# OK_p_edzesilova.net
KiCad netlist of a schematic drawn in EAGLE
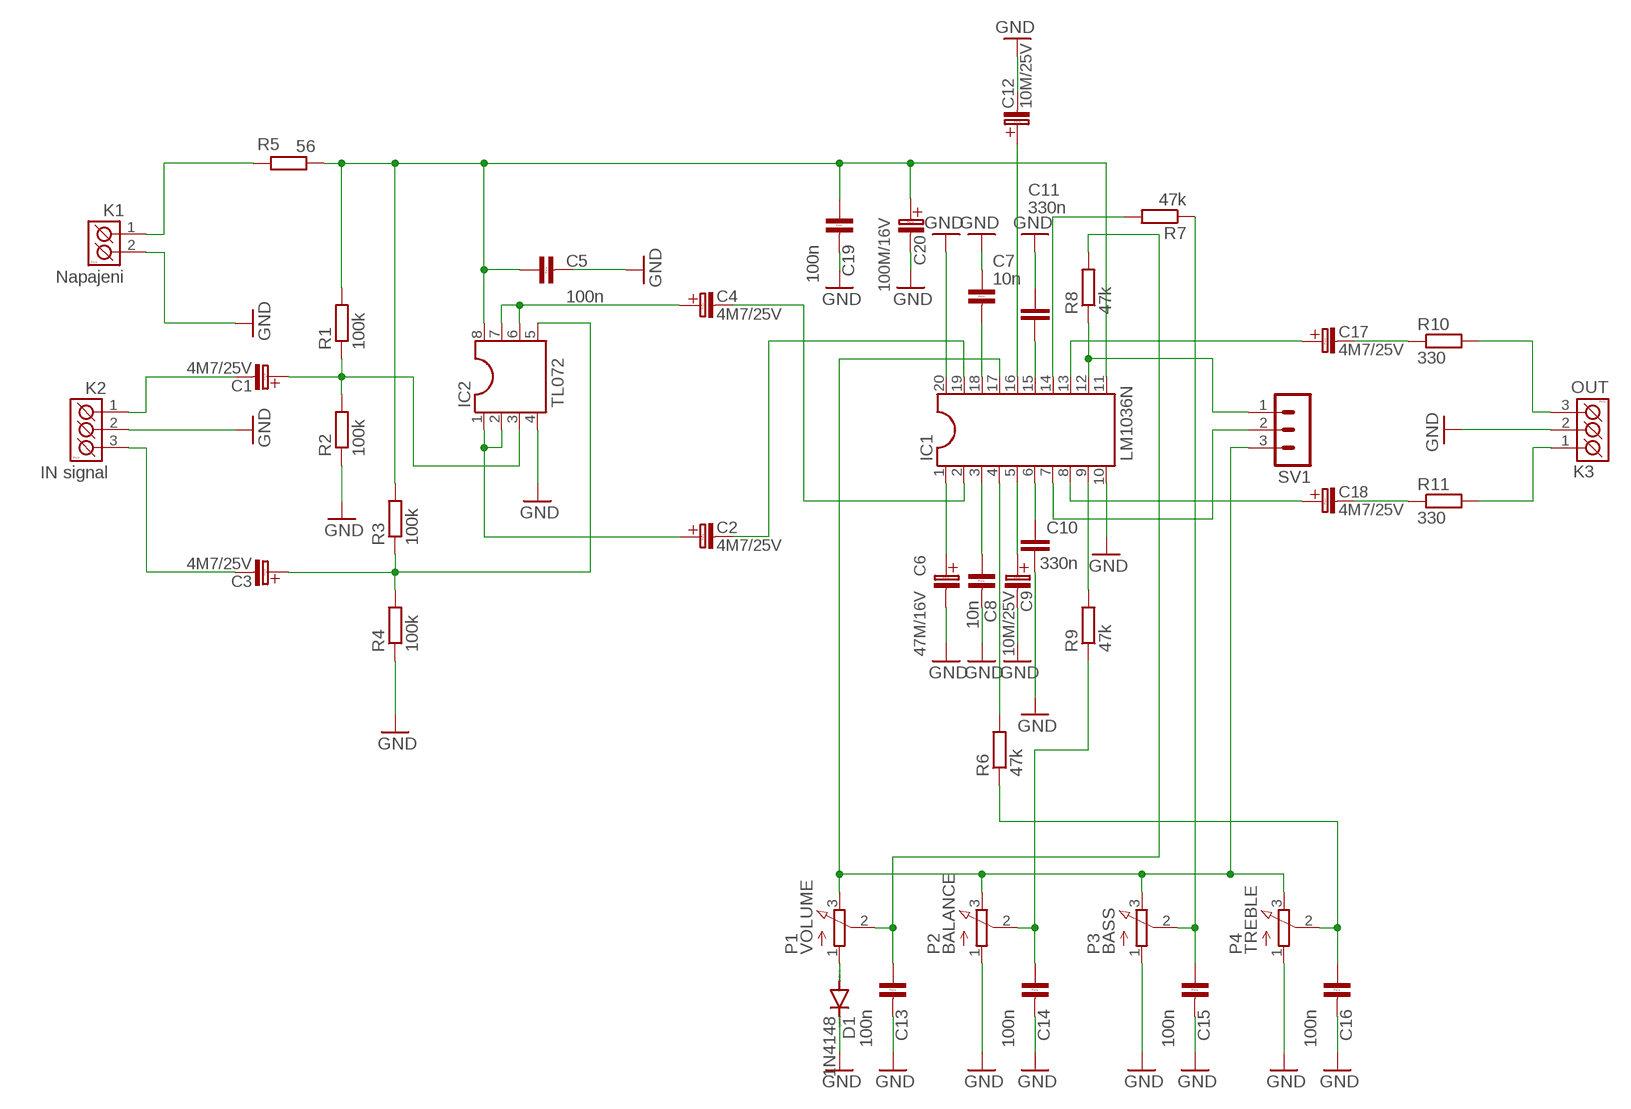
[diagram p0: schematic, sheet 1]

(export (version "E")
  (design (tool "Eeschema 10.0.6"))
  (components
    (comp (ref "C1")
      (value "4M7/25V")
      (footprint "eagle-import:C_EL_2")
      (libsource (lib "eagle-import") (part "4M7/63V"))
    )
    (comp (ref "C2")
      (value "4M7/25V")
      (footprint "eagle-import:C_EL_2")
      (libsource (lib "eagle-import") (part "4M7/63V"))
    )
    (comp (ref "C3")
      (value "4M7/25V")
      (footprint "eagle-import:C_EL_2")
      (libsource (lib "eagle-import") (part "4M7/63V"))
    )
    (comp (ref "C4")
      (value "4M7/25V")
      (footprint "eagle-import:C_EL_2")
      (libsource (lib "eagle-import") (part "4M7/63V"))
    )
    (comp (ref "C5")
      (value "100n")
      (footprint "eagle-import:RM5_2,5")
      (libsource (lib "eagle-import") (part "100N-J/63V"))
    )
    (comp (ref "C6")
      (value "47M/16V")
      (footprint "eagle-import:C_EL_2")
      (libsource (lib "eagle-import") (part "47M/10V"))
    )
    (comp (ref "C7")
      (value "10n")
      (footprint "eagle-import:RM5_2,5")
      (libsource (lib "eagle-import") (part "10N-J/63V"))
    )
    (comp (ref "C8")
      (value "10n")
      (footprint "eagle-import:RM5_2,5")
      (libsource (lib "eagle-import") (part "10N-J/63V"))
    )
    (comp (ref "C9")
      (value "10M/25V")
      (footprint "eagle-import:C_EL_2,5")
      (libsource (lib "eagle-import") (part "10M/100V"))
    )
    (comp (ref "C10")
      (value "330n")
      (footprint "eagle-import:C075-032X103")
      (libsource (lib "eagle-import") (part "C-EU075-032X103"))
    )
    (comp (ref "C11")
      (value "330n")
      (footprint "eagle-import:C075-032X103")
      (libsource (lib "eagle-import") (part "C-EU075-032X103"))
    )
    (comp (ref "C12")
      (value "10M/25V")
      (footprint "eagle-import:C_EL_2,5")
      (libsource (lib "eagle-import") (part "10M/100V"))
    )
    (comp (ref "C13")
      (value "100n")
      (footprint "eagle-import:RM5_2,5")
      (libsource (lib "eagle-import") (part "100N-J/63V"))
    )
    (comp (ref "C14")
      (value "100n")
      (footprint "eagle-import:RM5_2,5")
      (libsource (lib "eagle-import") (part "100N-J/63V"))
    )
    (comp (ref "C15")
      (value "100n")
      (footprint "eagle-import:RM5_2,5")
      (libsource (lib "eagle-import") (part "100N-J/63V"))
    )
    (comp (ref "C16")
      (value "100n")
      (footprint "eagle-import:RM5_2,5")
      (libsource (lib "eagle-import") (part "100N-J/63V"))
    )
    (comp (ref "C17")
      (value "4M7/25V")
      (footprint "eagle-import:C_EL_2")
      (libsource (lib "eagle-import") (part "4M7/63V"))
    )
    (comp (ref "C18")
      (value "4M7/25V")
      (footprint "eagle-import:C_EL_2")
      (libsource (lib "eagle-import") (part "4M7/63V"))
    )
    (comp (ref "C19")
      (value "100n")
      (footprint "eagle-import:RM5_2,5")
      (libsource (lib "eagle-import") (part "100N-J/63V"))
    )
    (comp (ref "C20")
      (value "100M/16V")
      (footprint "eagle-import:C_EL_3,5")
      (libsource (lib "eagle-import") (part "100M/50V"))
    )
    (comp (ref "D1")
      (value "1N4148")
      (footprint "eagle-import:DO35-7")
      (libsource (lib "eagle-import") (part "1N4148DO35-7"))
    )
    (comp (ref "IC1")
      (value "LM1036N")
      (footprint "eagle-import:DIL20")
      (libsource (lib "eagle-import") (part "DIL20"))
    )
    (comp (ref "IC2")
      (value "TL072")
      (footprint "eagle-import:DIL08")
      (libsource (lib "eagle-import") (part "DIL8"))
    )
    (comp (ref "K1")
      (value "Napajeni")
      (footprint "eagle-import:ARK500_2")
      (libsource (lib "eagle-import") (part "ARK500/2"))
    )
    (comp (ref "K2")
      (value "IN signal")
      (footprint "eagle-import:ARK500_3")
      (libsource (lib "eagle-import") (part "ARK500/3"))
    )
    (comp (ref "K3")
      (value "OUT")
      (footprint "eagle-import:ARK500_3")
      (libsource (lib "eagle-import") (part "ARK500/3"))
    )
    (comp (ref "P1")
      (value "VOLUME")
      (footprint "eagle-import:3RP_1610N")
      (libsource (lib "eagle-import") (part "3RP/1610N"))
    )
    (comp (ref "P2")
      (value "BALANCE")
      (footprint "eagle-import:3RP_1610N")
      (libsource (lib "eagle-import") (part "3RP/1610N"))
    )
    (comp (ref "P3")
      (value "BASS")
      (footprint "eagle-import:3RP_1610N")
      (libsource (lib "eagle-import") (part "3RP/1610N"))
    )
    (comp (ref "P4")
      (value "TREBLE")
      (footprint "eagle-import:3RP_1610N")
      (libsource (lib "eagle-import") (part "3RP/1610N"))
    )
    (comp (ref "R1")
      (value "100k")
      (footprint "eagle-import:0207_12")
      (libsource (lib "eagle-import") (part "R-EU_0207/12"))
    )
    (comp (ref "R2")
      (value "100k")
      (footprint "eagle-import:0204_7")
      (libsource (lib "eagle-import") (part "R-EU_0204/7"))
    )
    (comp (ref "R3")
      (value "100k")
      (footprint "eagle-import:0204_7")
      (libsource (lib "eagle-import") (part "R-EU_0204/7"))
    )
    (comp (ref "R4")
      (value "100k")
      (footprint "eagle-import:0204_7")
      (libsource (lib "eagle-import") (part "R-EU_0204/7"))
    )
    (comp (ref "R5")
      (value "56")
      (footprint "eagle-import:0204_7")
      (libsource (lib "eagle-import") (part "R-EU_0204/7"))
    )
    (comp (ref "R6")
      (value "47k")
      (footprint "eagle-import:0207_12")
      (libsource (lib "eagle-import") (part "R-EU_0207/12"))
    )
    (comp (ref "R7")
      (value "47k")
      (footprint "eagle-import:0207_12")
      (libsource (lib "eagle-import") (part "R-EU_0207/12"))
    )
    (comp (ref "R8")
      (value "47k")
      (footprint "eagle-import:0207_12")
      (libsource (lib "eagle-import") (part "R-EU_0207/12"))
    )
    (comp (ref "R9")
      (value "47k")
      (footprint "eagle-import:0207_12")
      (libsource (lib "eagle-import") (part "R-EU_0207/12"))
    )
    (comp (ref "R10")
      (value "330")
      (footprint "eagle-import:0204_7")
      (libsource (lib "eagle-import") (part "R-EU_0204/7"))
    )
    (comp (ref "R11")
      (value "330")
      (footprint "eagle-import:0207_12")
      (libsource (lib "eagle-import") (part "R-EU_0207/12"))
    )
    (comp (ref "SV1")
      (value "MA03-1")
      (footprint "eagle-import:MA03-1")
      (libsource (lib "eagle-import") (part "MA03-1"))
    )
  )
  (nets
    (net (code "1") (name "GND") (class "Default")
      (node (ref "C10") (pin "2") (pinfunction "2_2") (pintype "passive"))
      (node (ref "C11") (pin "1") (pinfunction "1_1") (pintype "passive"))
      (node (ref "C12") (pin "C-") (pinfunction "C_EL-_C-") (pintype "passive"))
      (node (ref "C13") (pin "2") (pinfunction "2_2") (pintype "passive"))
      (node (ref "C14") (pin "2") (pinfunction "2_2") (pintype "passive"))
      (node (ref "C15") (pin "2") (pinfunction "2_2") (pintype "passive"))
      (node (ref "C16") (pin "2") (pinfunction "2_2") (pintype "passive"))
      (node (ref "C19") (pin "2") (pinfunction "2_2") (pintype "passive"))
      (node (ref "C20") (pin "C-") (pinfunction "C_EL-_C-") (pintype "passive"))
      (node (ref "C5") (pin "2") (pinfunction "2_2") (pintype "passive"))
      (node (ref "C6") (pin "C-") (pinfunction "C_EL-_C-") (pintype "passive"))
      (node (ref "C7") (pin "1") (pinfunction "1_1") (pintype "passive"))
      (node (ref "C8") (pin "2") (pinfunction "2_2") (pintype "passive"))
      (node (ref "C9") (pin "C-") (pinfunction "C_EL-_C-") (pintype "passive"))
      (node (ref "D1") (pin "C") (pinfunction "C_C") (pintype "passive"))
      (node (ref "IC1") (pin "10") (pinfunction "10_10") (pintype "passive"))
      (node (ref "IC1") (pin "20") (pinfunction "20_20") (pintype "passive"))
      (node (ref "IC2") (pin "4") (pinfunction "4_4") (pintype "passive"))
      (node (ref "K1") (pin "2") (pinfunction "K2_2") (pintype "passive"))
      (node (ref "K2") (pin "2") (pinfunction "K2_2") (pintype "passive"))
      (node (ref "K3") (pin "2") (pinfunction "K2_2") (pintype "passive"))
      (node (ref "P2") (pin "1") (pinfunction "A_1") (pintype "passive"))
      (node (ref "P3") (pin "1") (pinfunction "A_1") (pintype "passive"))
      (node (ref "P4") (pin "1") (pinfunction "A_1") (pintype "passive"))
      (node (ref "R2") (pin "1") (pinfunction "1_1") (pintype "passive"))
      (node (ref "R4") (pin "1") (pinfunction "1_1") (pintype "passive"))
    )
    (net (code "2") (name "Net-(C1-C_EL+)") (class "Default")
      (node (ref "C1") (pin "C+") (pinfunction "C_EL+_C+") (pintype "passive"))
      (node (ref "IC2") (pin "3") (pinfunction "3_3") (pintype "passive"))
      (node (ref "R1") (pin "1") (pinfunction "1_1") (pintype "passive"))
      (node (ref "R2") (pin "2") (pinfunction "2_2") (pintype "passive"))
    )
    (net (code "3") (name "Net-(C1-C_EL-)") (class "Default")
      (node (ref "C1") (pin "C-") (pinfunction "C_EL-_C-") (pintype "passive"))
      (node (ref "K2") (pin "1") (pinfunction "K1_1") (pintype "passive"))
    )
    (net (code "4") (name "Net-(C2-C_EL+)") (class "Default")
      (node (ref "C2") (pin "C+") (pinfunction "C_EL+_C+") (pintype "passive"))
      (node (ref "IC2") (pin "1") (pinfunction "1_1") (pintype "passive"))
      (node (ref "IC2") (pin "2") (pinfunction "2_2") (pintype "passive"))
    )
    (net (code "5") (name "Net-(C2-C_EL-)") (class "Default")
      (node (ref "C2") (pin "C-") (pinfunction "C_EL-_C-") (pintype "passive"))
      (node (ref "IC1") (pin "19") (pinfunction "19_19") (pintype "passive"))
    )
    (net (code "6") (name "Net-(C3-C_EL+)") (class "Default")
      (node (ref "C3") (pin "C+") (pinfunction "C_EL+_C+") (pintype "passive"))
      (node (ref "IC2") (pin "5") (pinfunction "5_5") (pintype "passive"))
      (node (ref "R3") (pin "1") (pinfunction "1_1") (pintype "passive"))
      (node (ref "R4") (pin "2") (pinfunction "2_2") (pintype "passive"))
    )
    (net (code "7") (name "Net-(C3-C_EL-)") (class "Default")
      (node (ref "C3") (pin "C-") (pinfunction "C_EL-_C-") (pintype "passive"))
      (node (ref "K2") (pin "3") (pinfunction "K3_3") (pintype "passive"))
    )
    (net (code "8") (name "Net-(C4-C_EL+)") (class "Default")
      (node (ref "C4") (pin "C+") (pinfunction "C_EL+_C+") (pintype "passive"))
      (node (ref "IC2") (pin "6") (pinfunction "6_6") (pintype "passive"))
      (node (ref "IC2") (pin "7") (pinfunction "7_7") (pintype "passive"))
    )
    (net (code "9") (name "Net-(C4-C_EL-)") (class "Default")
      (node (ref "C4") (pin "C-") (pinfunction "C_EL-_C-") (pintype "passive"))
      (node (ref "IC1") (pin "2") (pinfunction "2_2") (pintype "passive"))
    )
    (net (code "10") (name "Net-(C6-C_EL+)") (class "Default")
      (node (ref "C6") (pin "C+") (pinfunction "C_EL+_C+") (pintype "passive"))
      (node (ref "IC1") (pin "1") (pinfunction "1_1") (pintype "passive"))
    )
    (net (code "11") (name "Net-(C7-Pad2)") (class "Default")
      (node (ref "C7") (pin "2") (pinfunction "2_2") (pintype "passive"))
      (node (ref "IC1") (pin "18") (pinfunction "18_18") (pintype "passive"))
    )
    (net (code "12") (name "Net-(C8-Pad1)") (class "Default")
      (node (ref "C8") (pin "1") (pinfunction "1_1") (pintype "passive"))
      (node (ref "IC1") (pin "3") (pinfunction "3_3") (pintype "passive"))
    )
    (net (code "13") (name "Net-(C9-C_EL+)") (class "Default")
      (node (ref "C9") (pin "C+") (pinfunction "C_EL+_C+") (pintype "passive"))
      (node (ref "IC1") (pin "5") (pinfunction "5_5") (pintype "passive"))
    )
    (net (code "14") (name "Net-(C10-Pad1)") (class "Default")
      (node (ref "C10") (pin "1") (pinfunction "1_1") (pintype "passive"))
      (node (ref "IC1") (pin "6") (pinfunction "6_6") (pintype "passive"))
    )
    (net (code "15") (name "Net-(C11-Pad2)") (class "Default")
      (node (ref "C11") (pin "2") (pinfunction "2_2") (pintype "passive"))
      (node (ref "IC1") (pin "15") (pinfunction "15_15") (pintype "passive"))
    )
    (net (code "16") (name "Net-(C12-C_EL+)") (class "Default")
      (node (ref "C12") (pin "C+") (pinfunction "C_EL+_C+") (pintype "passive"))
      (node (ref "IC1") (pin "16") (pinfunction "16_16") (pintype "passive"))
    )
    (net (code "17") (name "Net-(C17-C_EL+)") (class "Default")
      (node (ref "C17") (pin "C+") (pinfunction "C_EL+_C+") (pintype "passive"))
      (node (ref "IC1") (pin "13") (pinfunction "13_13") (pintype "passive"))
    )
    (net (code "18") (name "Net-(C17-C_EL-)") (class "Default")
      (node (ref "C17") (pin "C-") (pinfunction "C_EL-_C-") (pintype "passive"))
      (node (ref "R10") (pin "1") (pinfunction "1_1") (pintype "passive"))
    )
    (net (code "19") (name "Net-(C18-C_EL+)") (class "Default")
      (node (ref "C18") (pin "C+") (pinfunction "C_EL+_C+") (pintype "passive"))
      (node (ref "IC1") (pin "8") (pinfunction "8_8") (pintype "passive"))
    )
    (net (code "20") (name "Net-(C18-C_EL-)") (class "Default")
      (node (ref "C18") (pin "C-") (pinfunction "C_EL-_C-") (pintype "passive"))
      (node (ref "R11") (pin "1") (pinfunction "1_1") (pintype "passive"))
    )
    (net (code "21") (name "Net-(C20-C_EL+)") (class "Default")
      (node (ref "C19") (pin "1") (pinfunction "1_1") (pintype "passive"))
      (node (ref "C20") (pin "C+") (pinfunction "C_EL+_C+") (pintype "passive"))
      (node (ref "C5") (pin "1") (pinfunction "1_1") (pintype "passive"))
      (node (ref "IC1") (pin "11") (pinfunction "11_11") (pintype "passive"))
      (node (ref "IC2") (pin "8") (pinfunction "8_8") (pintype "passive"))
      (node (ref "R1") (pin "2") (pinfunction "2_2") (pintype "passive"))
      (node (ref "R3") (pin "2") (pinfunction "2_2") (pintype "passive"))
      (node (ref "R5") (pin "1") (pinfunction "1_1") (pintype "passive"))
    )
    (net (code "22") (name "Net-(IC1-Pad4)") (class "Default")
      (node (ref "IC1") (pin "4") (pinfunction "4_4") (pintype "passive"))
      (node (ref "R6") (pin "2") (pinfunction "2_2") (pintype "passive"))
    )
    (net (code "23") (name "Net-(IC1-Pad7)") (class "Default")
      (node (ref "IC1") (pin "7") (pinfunction "7_7") (pintype "passive"))
      (node (ref "SV1") (pin "2") (pinfunction "2_2") (pintype "passive"))
    )
    (net (code "24") (name "Net-(IC1-Pad9)") (class "Default")
      (node (ref "IC1") (pin "9") (pinfunction "9_9") (pintype "passive"))
      (node (ref "R9") (pin "2") (pinfunction "2_2") (pintype "passive"))
    )
    (net (code "25") (name "Net-(IC1-Pad12)") (class "Default")
      (node (ref "IC1") (pin "12") (pinfunction "12_12") (pintype "passive"))
      (node (ref "R8") (pin "1") (pinfunction "1_1") (pintype "passive"))
      (node (ref "SV1") (pin "1") (pinfunction "1_1") (pintype "passive"))
    )
    (net (code "26") (name "Net-(IC1-Pad14)") (class "Default")
      (node (ref "IC1") (pin "14") (pinfunction "14_14") (pintype "passive"))
      (node (ref "R7") (pin "2") (pinfunction "2_2") (pintype "passive"))
    )
    (net (code "27") (name "Net-(K1-K1)") (class "Default")
      (node (ref "K1") (pin "1") (pinfunction "K1_1") (pintype "passive"))
      (node (ref "R5") (pin "2") (pinfunction "2_2") (pintype "passive"))
    )
    (net (code "28") (name "Net-(K3-K1)") (class "Default")
      (node (ref "K3") (pin "1") (pinfunction "K1_1") (pintype "passive"))
      (node (ref "R11") (pin "2") (pinfunction "2_2") (pintype "passive"))
    )
    (net (code "29") (name "Net-(K3-K3)") (class "Default")
      (node (ref "K3") (pin "3") (pinfunction "K3_3") (pintype "passive"))
      (node (ref "R10") (pin "2") (pinfunction "2_2") (pintype "passive"))
    )
    (net (code "30") (name "Net-(P1-A)") (class "Default")
      (node (ref "D1") (pin "A") (pinfunction "A_A") (pintype "passive"))
      (node (ref "P1") (pin "1") (pinfunction "A_1") (pintype "passive"))
    )
    (net (code "31") (name "Net-(P1-E)") (class "Default")
      (node (ref "IC1") (pin "17") (pinfunction "17_17") (pintype "passive"))
      (node (ref "P1") (pin "3") (pinfunction "E_3") (pintype "passive"))
      (node (ref "P2") (pin "3") (pinfunction "E_3") (pintype "passive"))
      (node (ref "P3") (pin "3") (pinfunction "E_3") (pintype "passive"))
      (node (ref "P4") (pin "3") (pinfunction "E_3") (pintype "passive"))
      (node (ref "SV1") (pin "3") (pinfunction "3_3") (pintype "passive"))
    )
    (net (code "32") (name "Net-(P1-S)") (class "Default")
      (node (ref "C13") (pin "1") (pinfunction "1_1") (pintype "passive"))
      (node (ref "P1") (pin "2") (pinfunction "S_2") (pintype "passive"))
      (node (ref "R8") (pin "2") (pinfunction "2_2") (pintype "passive"))
    )
    (net (code "33") (name "Net-(P2-S)") (class "Default")
      (node (ref "C14") (pin "1") (pinfunction "1_1") (pintype "passive"))
      (node (ref "P2") (pin "2") (pinfunction "S_2") (pintype "passive"))
      (node (ref "R9") (pin "1") (pinfunction "1_1") (pintype "passive"))
    )
    (net (code "34") (name "Net-(P3-S)") (class "Default")
      (node (ref "C15") (pin "1") (pinfunction "1_1") (pintype "passive"))
      (node (ref "P3") (pin "2") (pinfunction "S_2") (pintype "passive"))
      (node (ref "R7") (pin "1") (pinfunction "1_1") (pintype "passive"))
    )
    (net (code "35") (name "Net-(P4-S)") (class "Default")
      (node (ref "C16") (pin "1") (pinfunction "1_1") (pintype "passive"))
      (node (ref "P4") (pin "2") (pinfunction "S_2") (pintype "passive"))
      (node (ref "R6") (pin "1") (pinfunction "1_1") (pintype "passive"))
    )
  )
)
